# Stepper_Motor5.net
KiCad netlist of a schematic drawn in Altium Designer
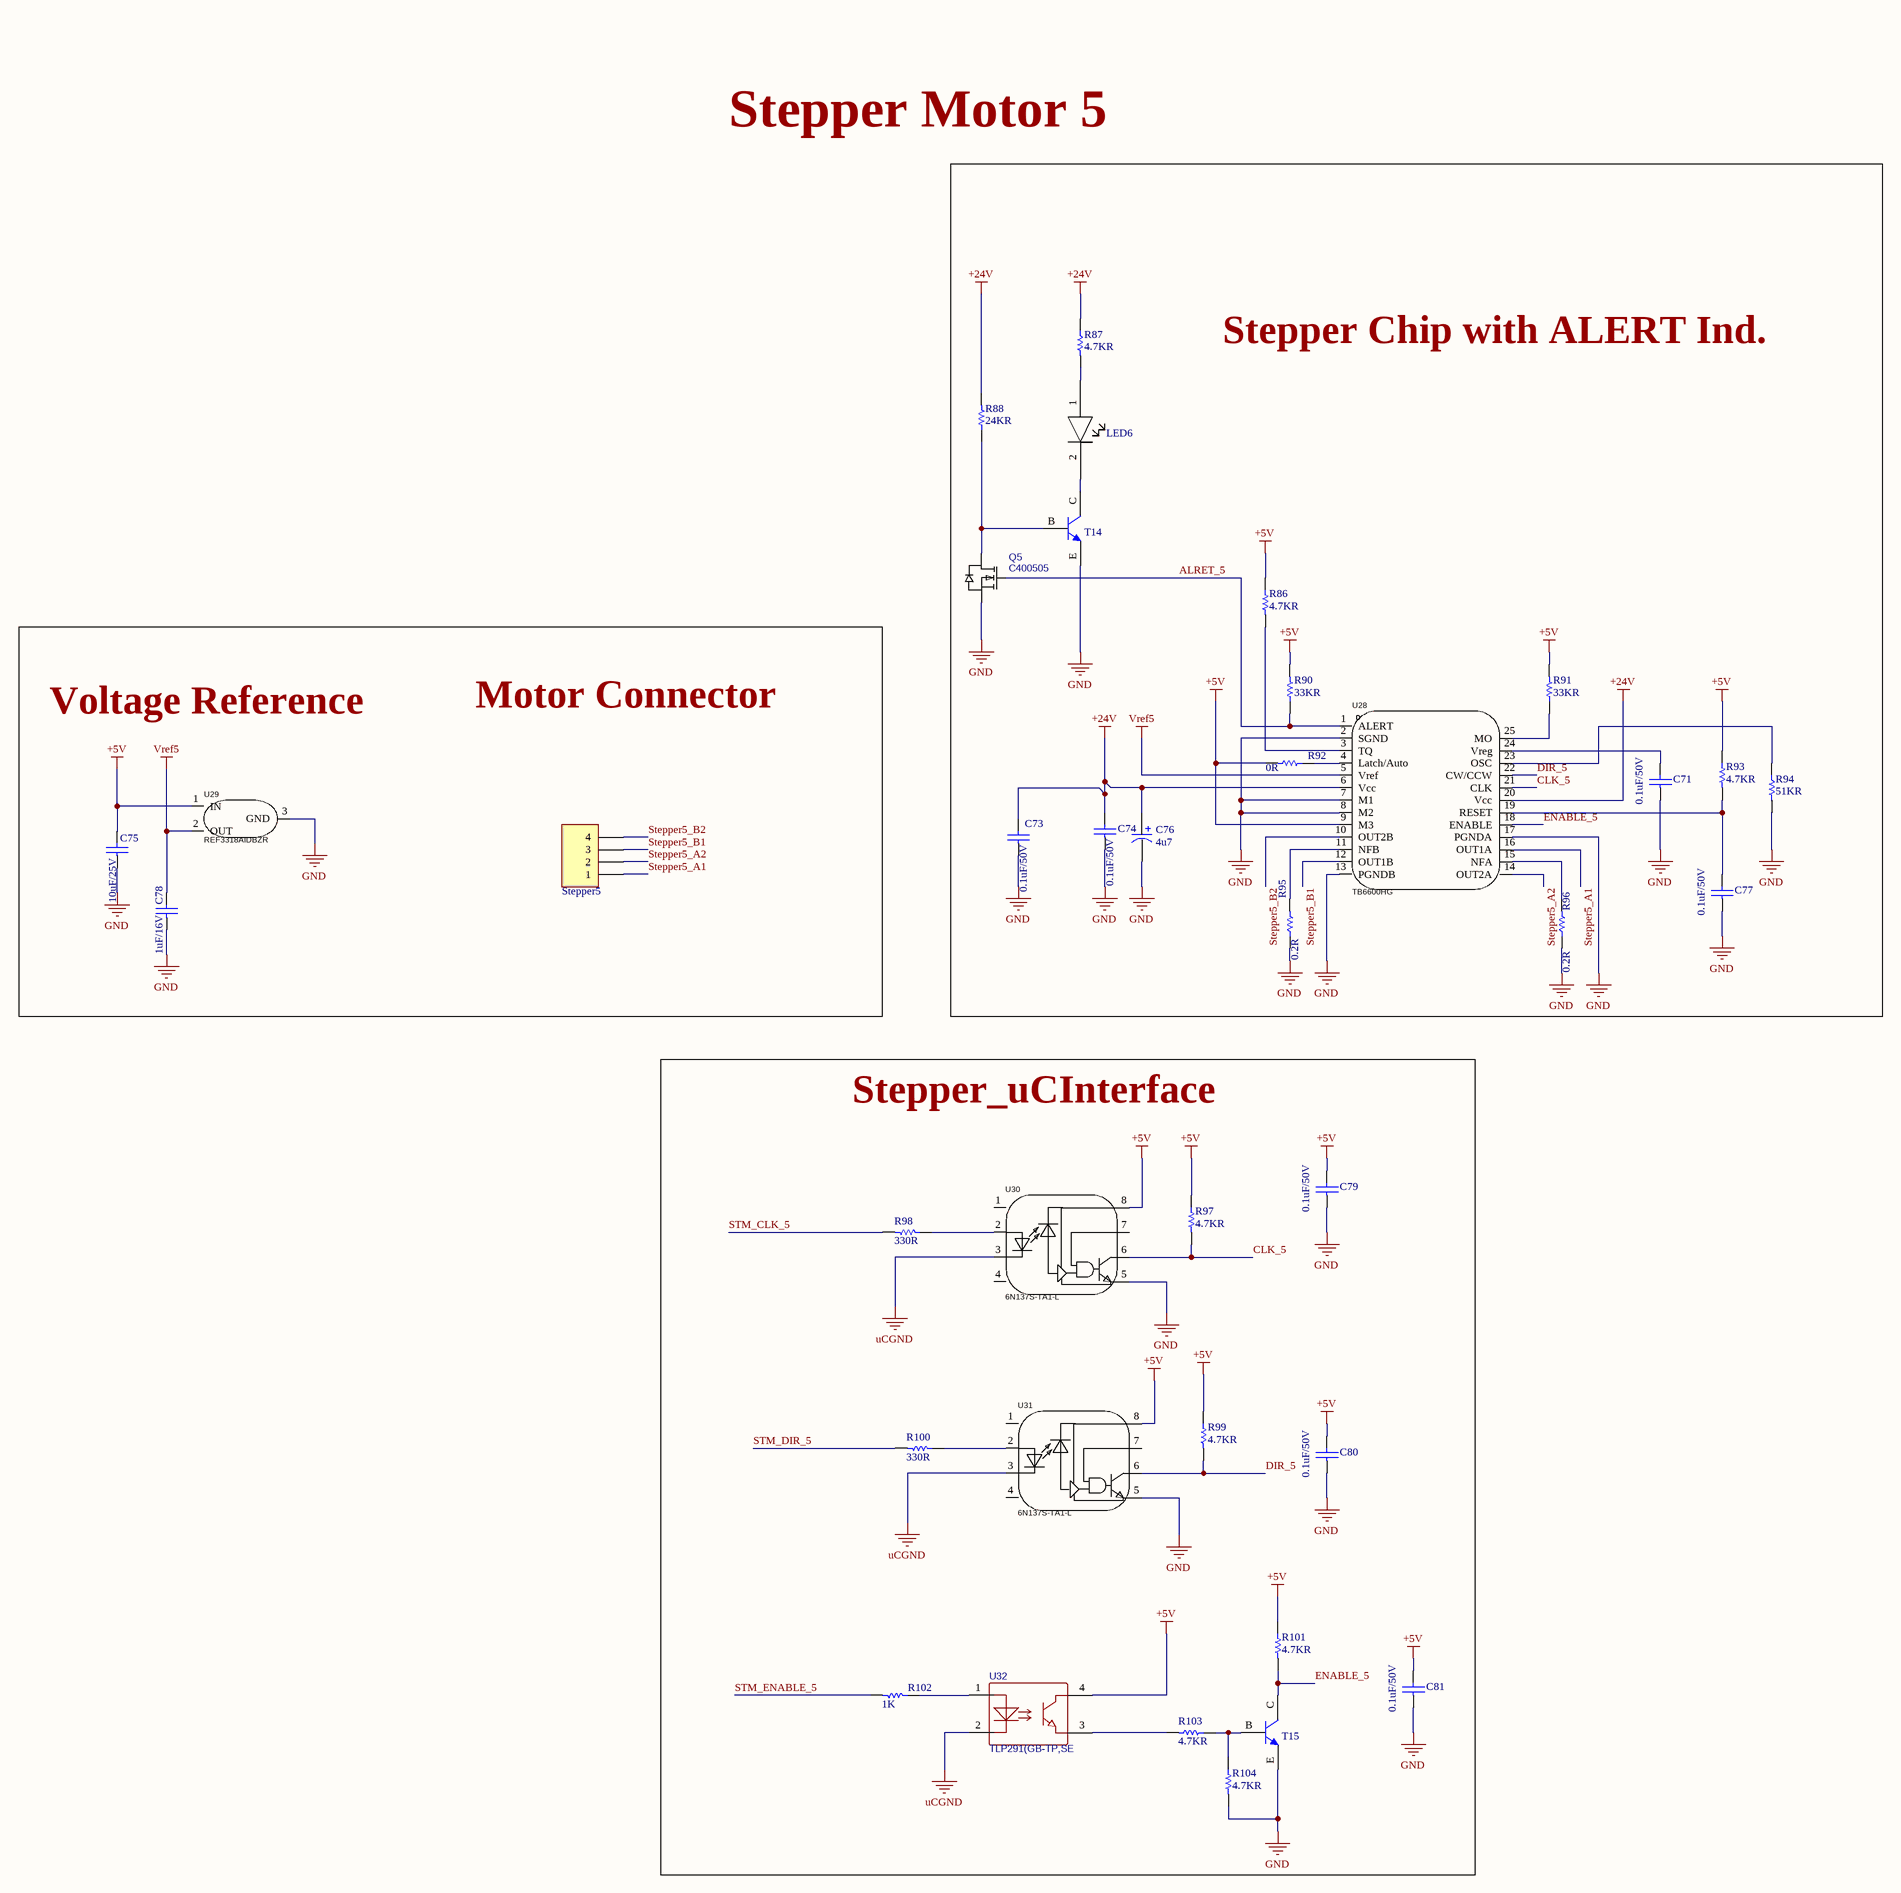
[diagram p0: Stepper Motor5.SchDoc]

(export (version "E")
  (design (tool "Eeschema 10.0.6"))
  (components
    (comp (ref "C71")
      (value "0.1uF/50V")
      (footprint "PCBComponent_1")
      (description "C1591")
      (fields (field (name "CREATED BY") "NourAldin"))
      (libsource (lib "0603 Capacitor") (part "0603 Capacitor"))
    )
    (comp (ref "C73")
      (value "0.1uF/50V")
      (footprint "PCBComponent_1")
      (description "C1591")
      (fields (field (name "CREATED BY") "NourAldin"))
      (libsource (lib "0603 Capacitor") (part "0603 Capacitor"))
    )
    (comp (ref "C74")
      (value "0.1uF/50V")
      (footprint "PCBComponent_1")
      (description "C1591")
      (fields (field (name "CREATED BY") "NourAldin"))
      (libsource (lib "0603 Capacitor") (part "0603 Capacitor"))
    )
    (comp (ref "C75")
      (value "10uF/25V")
      (footprint "PCBComponent_1")
      (description "C96446")
      (fields (field (name "CREATED BY") "NourAldin"))
      (libsource (lib "0603 Capacitor") (part "0603 Capacitor"))
    )
    (comp (ref "C76")
      (value "4u7")
      (footprint "CAPLEAD_D6.3mm")
      (description "C2691843")
      (fields
        (field (name "MANUFACTURER") "KEMET")
        (field (name "MANUFACTURER PART NUMBER") "A759EQ475M2AAAE160")
      )
      (libsource (lib "GlobalLib") (part "A759EQ475M2AAAE160"))
    )
    (comp (ref "C77")
      (value "0.1uF/50V")
      (footprint "PCBComponent_1")
      (description "C1591")
      (fields (field (name "CREATED BY") "NourAldin"))
      (libsource (lib "0603 Capacitor") (part "0603 Capacitor"))
    )
    (comp (ref "C78")
      (value "1uF/16V")
      (footprint "PCBComponent_1")
      (description "C1592")
      (fields (field (name "CREATED BY") "NourAldin"))
      (libsource (lib "0603 Capacitor") (part "0603 Capacitor"))
    )
    (comp (ref "C79")
      (value "0.1uF/50V")
      (footprint "PCBComponent_1")
      (description "C1591")
      (fields (field (name "CREATED BY") "NourAldin"))
      (libsource (lib "0603 Capacitor") (part "0603 Capacitor"))
    )
    (comp (ref "C80")
      (value "0.1uF/50V")
      (footprint "PCBComponent_1")
      (description "C1591")
      (fields (field (name "CREATED BY") "NourAldin"))
      (libsource (lib "0603 Capacitor") (part "0603 Capacitor"))
    )
    (comp (ref "C81")
      (value "0.1uF/50V")
      (footprint "PCBComponent_1")
      (description "C1591")
      (fields (field (name "CREATED BY") "NourAldin"))
      (libsource (lib "0603 Capacitor") (part "0603 Capacitor"))
    )
    (comp (ref "LED6")
      (value "1206 LED")
      (footprint "1206 LED")
      (description "C434438")
      (fields (field (name "CREATED BY") "NourAldin"))
      (libsource (lib "1206 LED") (part "1206 LED"))
    )
    (comp (ref "Q5")
      (value "C400505")
      (footprint "SOT-23-3_L2.9-W1.3-P1.90-LS2.4-BR")
      (fields
        (field (name "MANUFACTURER") "YANGJIE(扬杰)")
        (field (name "MANUFACTURER PART") "BSS138")
        (field (name "CONTRIBUTOR") "LCSC")
      )
      (libsource (lib "DIVERSE") (part "BSS138_MOSFET"))
    )
    (comp (ref "R86")
      (value "4.7KR")
      (footprint "R0402")
      (description "C105871")
      (libsource (lib "DIVERSE") (part "0402 Resistor"))
    )
    (comp (ref "R87")
      (value "4.7KR")
      (footprint "R0402")
      (description "C105871")
      (libsource (lib "DIVERSE") (part "0402 Resistor"))
    )
    (comp (ref "R88")
      (value "24KR")
      (footprint "RESC1608X06N")
      (description "C2930081")
      (fields (field (name "CREATED BY") "NourAldin"))
      (libsource (lib "0603 Resistor") (part "0603 Resistor"))
    )
    (comp (ref "R90")
      (value "33KR")
      (footprint "RESC1608X06N")
      (description "C126359")
      (fields (field (name "CREATED BY") "NourAldin"))
      (libsource (lib "0603 Resistor") (part "0603 Resistor"))
    )
    (comp (ref "R91")
      (value "33KR")
      (footprint "RESC1608X06N")
      (description "C126359")
      (fields (field (name "CREATED BY") "NourAldin"))
      (libsource (lib "0603 Resistor") (part "0603 Resistor"))
    )
    (comp (ref "R92")
      (value "0R")
      (footprint "RESC1608X06N")
      (description "C100044")
      (fields (field (name "CREATED BY") "NourAldin"))
      (libsource (lib "0603 Resistor") (part "0603 Resistor"))
    )
    (comp (ref "R93")
      (value "4.7KR")
      (footprint "R0402")
      (description "C105871")
      (libsource (lib "DIVERSE") (part "0402 Resistor"))
    )
    (comp (ref "R94")
      (value "51KR")
      (footprint "R0402")
      (description "C107230")
      (libsource (lib "DIVERSE") (part "0402 Resistor"))
    )
    (comp (ref "R95")
      (value "0.2R")
      (footprint "RESC6431X12N")
      (description "C2903473")
      (fields (field (name "CREATED BY") "NourAldin"))
      (libsource (lib "2512 Resistor") (part "2512 Resistor"))
    )
    (comp (ref "R96")
      (value "0.2R")
      (footprint "RESC6431X12N")
      (description "C2903473")
      (fields (field (name "CREATED BY") "NourAldin"))
      (libsource (lib "2512 Resistor") (part "2512 Resistor"))
    )
    (comp (ref "R97")
      (value "4.7KR")
      (footprint "R0402")
      (description "C105871")
      (libsource (lib "DIVERSE") (part "0402 Resistor"))
    )
    (comp (ref "R98")
      (value "330R")
      (footprint "R0402")
      (description "C105875")
      (libsource (lib "DIVERSE") (part "0402 Resistor"))
    )
    (comp (ref "R99")
      (value "4.7KR")
      (footprint "R0402")
      (description "C105871")
      (libsource (lib "DIVERSE") (part "0402 Resistor"))
    )
    (comp (ref "R100")
      (value "330R")
      (footprint "R0402")
      (description "C105875")
      (libsource (lib "DIVERSE") (part "0402 Resistor"))
    )
    (comp (ref "R101")
      (value "4.7KR")
      (footprint "R0402")
      (description "C105871")
      (libsource (lib "DIVERSE") (part "0402 Resistor"))
    )
    (comp (ref "R102")
      (value "1K")
      (footprint "R0402")
      (description "C106235")
      (libsource (lib "DIVERSE") (part "0402 Resistor"))
    )
    (comp (ref "R103")
      (value "4.7KR")
      (footprint "R0402")
      (description "C105871")
      (libsource (lib "DIVERSE") (part "0402 Resistor"))
    )
    (comp (ref "R104")
      (value "4.7KR")
      (footprint "R0402")
      (description "C105871")
      (libsource (lib "DIVERSE") (part "0402 Resistor"))
    )
    (comp (ref "Stepper5")
      (value "Header 4 Pin Polar")
      (footprint "PCBComponent_1")
      (description "C144395")
      (libsource (lib "Header 4 Pin Polar") (part "Header 4 Pin Polar"))
    )
    (comp (ref "T14")
      (value "MMBT3904 Transistor")
      (footprint "MMBT3904")
      (description "C108429")
      (fields (field (name "CREATED BY") "NourAldin"))
      (libsource (lib "MMBT3904 Transistor") (part "MMBT3904 Transistor"))
    )
    (comp (ref "T15")
      (value "MMBT3904 Transistor")
      (footprint "MMBT3904")
      (description "C108429")
      (fields (field (name "CREATED BY") "NourAldin"))
      (libsource (lib "MMBT3904 Transistor") (part "MMBT3904 Transistor"))
    )
    (comp (ref "U28")
      (value "TB6600HG")
      (footprint "HZIP25-P-1.0_TB6600HG - HEATSINK")
      (description "C66042")
      (fields (field (name "MANUFACTURER") "TOSHIBA(东芝)"))
      (libsource (lib "LIB") (part "TB6600HG"))
    )
    (comp (ref "U29")
      (value "REF3318AIDBZR")
      (footprint "SOT-23-3_L2.9-W1.3-P1.90-LS2.4-BR")
      (description "C115877")
      (fields (field (name "MANUFACTURER") "TI(德州仪器)") (field (name "TOLERANCE") "±0.15%"))
      (libsource (lib "LIB") (part "REF3318AIDBZR"))
    )
    (comp (ref "U30")
      (value "6N137S-TA1-L")
      (footprint "SOP-8_L9.8-W6.6-P2.54-LS10.3-BL")
      (description "C92651")
      (fields (field (name "MANUFACTURER") "LITEON(光宝)"))
      (libsource (lib "LIB") (part "6N137S-TA1-L"))
    )
    (comp (ref "U31")
      (value "6N137S-TA1-L")
      (footprint "SOP-8_L9.8-W6.6-P2.54-LS10.3-BL")
      (description "C92651")
      (fields (field (name "MANUFACTURER") "LITEON(光宝)"))
      (libsource (lib "LIB") (part "6N137S-TA1-L"))
    )
    (comp (ref "U32")
      (value "TLP291(GB-TP,SE")
      (footprint "SOP-4-1.27mm")
      (description "C55144")
      (libsource (lib "CO2_Lib") (part "TLP291(GB-TP,SE(T"))
    )
  )
  (nets
    (net (code "1") (name "+5V") (class "Default")
      (node (ref "C75") (pin "2") (pinfunction "2_2") (pintype "passive"))
      (node (ref "C79") (pin "2") (pinfunction "2_2") (pintype "passive"))
      (node (ref "C80") (pin "2") (pinfunction "2_2") (pintype "passive"))
      (node (ref "C81") (pin "2") (pinfunction "2_2") (pintype "passive"))
      (node (ref "R101") (pin "1") (pinfunction "1_1") (pintype "passive"))
      (node (ref "R86") (pin "1") (pinfunction "1_1") (pintype "passive"))
      (node (ref "R90") (pin "2") (pinfunction "2_2") (pintype "passive"))
      (node (ref "R91") (pin "2") (pinfunction "2_2") (pintype "passive"))
      (node (ref "R92") (pin "2") (pinfunction "2_2") (pintype "passive"))
      (node (ref "R93") (pin "1") (pinfunction "1_1") (pintype "passive"))
      (node (ref "R97") (pin "1") (pinfunction "1_1") (pintype "passive"))
      (node (ref "R99") (pin "1") (pinfunction "1_1") (pintype "passive"))
      (node (ref "U28") (pin "9") (pinfunction "M3_9") (pintype "passive"))
      (node (ref "U29") (pin "1") (pinfunction "IN_1") (pintype "passive"))
      (node (ref "U30") (pin "8") (pinfunction "8_8") (pintype "passive"))
      (node (ref "U31") (pin "8") (pinfunction "8_8") (pintype "passive"))
      (node (ref "U32") (pin "4") (pinfunction "4_4") (pintype "passive"))
    )
    (net (code "2") (name "+24V") (class "Default")
      (node (ref "C73") (pin "2") (pinfunction "2_2") (pintype "passive"))
      (node (ref "C74") (pin "2") (pinfunction "2_2") (pintype "passive"))
      (node (ref "C76") (pin "1") (pinfunction "1_1") (pintype "passive"))
      (node (ref "R87") (pin "1") (pinfunction "1_1") (pintype "passive"))
      (node (ref "R88") (pin "2") (pinfunction "2_2") (pintype "passive"))
      (node (ref "U28") (pin "20") (pinfunction "Vcc_20") (pintype "passive"))
      (node (ref "U28") (pin "6") (pinfunction "Vcc_6") (pintype "passive"))
    )
    (net (code "3") (name "/ALRET_5") (class "Default")
      (node (ref "Q5") (pin "1") (pinfunction "G_1") (pintype "passive"))
      (node (ref "R90") (pin "1") (pinfunction "1_1") (pintype "passive"))
      (node (ref "U28") (pin "1") (pinfunction "ALERT_1") (pintype "passive"))
    )
    (net (code "4") (name "/CLK_5") (class "Default")
      (node (ref "R97") (pin "2") (pinfunction "2_2") (pintype "passive"))
      (node (ref "U28") (pin "21") (pinfunction "CLK_21") (pintype "passive"))
      (node (ref "U30") (pin "6") (pinfunction "6_6") (pintype "passive"))
    )
    (net (code "5") (name "/DIR_5") (class "Default")
      (node (ref "R99") (pin "2") (pinfunction "2_2") (pintype "passive"))
      (node (ref "U28") (pin "22") (pinfunction "CW/CCW_22") (pintype "passive"))
      (node (ref "U31") (pin "6") (pinfunction "6_6") (pintype "passive"))
    )
    (net (code "6") (name "/ENABLE_5") (class "Default")
      (node (ref "R101") (pin "2") (pinfunction "2_2") (pintype "passive"))
      (node (ref "T15") (pin "C") (pinfunction "C_C") (pintype "passive"))
      (node (ref "U28") (pin "18") (pinfunction "ENABLE_18") (pintype "passive"))
    )
    (net (code "7") (name "/STM_CLK_5") (class "Default")
      (node (ref "R98") (pin "2") (pinfunction "2_2") (pintype "passive"))
    )
    (net (code "8") (name "/STM_DIR_5") (class "Default")
      (node (ref "R100") (pin "2") (pinfunction "2_2") (pintype "passive"))
    )
    (net (code "9") (name "/STM_ENABLE_5") (class "Default")
      (node (ref "R102") (pin "2") (pinfunction "2_2") (pintype "passive"))
    )
    (net (code "10") (name "/Stepper5_A1") (class "Default")
      (node (ref "Stepper5") (pin "1") (pinfunction "1_1") (pintype "passive"))
      (node (ref "U28") (pin "16") (pinfunction "OUT1A_16") (pintype "passive"))
    )
    (net (code "11") (name "/Stepper5_A2") (class "Default")
      (node (ref "Stepper5") (pin "2") (pinfunction "2_2") (pintype "passive"))
      (node (ref "U28") (pin "14") (pinfunction "OUT2A_14") (pintype "passive"))
    )
    (net (code "12") (name "/Stepper5_B1") (class "Default")
      (node (ref "Stepper5") (pin "3") (pinfunction "3_3") (pintype "passive"))
      (node (ref "U28") (pin "12") (pinfunction "OUT1B_12") (pintype "passive"))
    )
    (net (code "13") (name "/Stepper5_B2") (class "Default")
      (node (ref "Stepper5") (pin "4") (pinfunction "4_4") (pintype "passive"))
      (node (ref "U28") (pin "10") (pinfunction "OUT2B_10") (pintype "passive"))
    )
    (net (code "14") (name "GND") (class "Default")
      (node (ref "C71") (pin "1") (pinfunction "1_1") (pintype "passive"))
      (node (ref "C73") (pin "1") (pinfunction "1_1") (pintype "passive"))
      (node (ref "C74") (pin "1") (pinfunction "1_1") (pintype "passive"))
      (node (ref "C75") (pin "1") (pinfunction "1_1") (pintype "passive"))
      (node (ref "C76") (pin "2") (pinfunction "2_2") (pintype "passive"))
      (node (ref "C77") (pin "1") (pinfunction "1_1") (pintype "passive"))
      (node (ref "C78") (pin "1") (pinfunction "1_1") (pintype "passive"))
      (node (ref "C79") (pin "1") (pinfunction "1_1") (pintype "passive"))
      (node (ref "C80") (pin "1") (pinfunction "1_1") (pintype "passive"))
      (node (ref "C81") (pin "1") (pinfunction "1_1") (pintype "passive"))
      (node (ref "Q5") (pin "2") (pinfunction "S_2") (pintype "passive"))
      (node (ref "R104") (pin "2") (pinfunction "2_2") (pintype "passive"))
      (node (ref "R94") (pin "2") (pinfunction "2_2") (pintype "passive"))
      (node (ref "R95") (pin "1") (pinfunction "1_1") (pintype "passive"))
      (node (ref "R96") (pin "1") (pinfunction "1_1") (pintype "passive"))
      (node (ref "T14") (pin "E") (pinfunction "E_E") (pintype "passive"))
      (node (ref "T15") (pin "E") (pinfunction "E_E") (pintype "passive"))
      (node (ref "U28") (pin "13") (pinfunction "PGNDB_13") (pintype "passive"))
      (node (ref "U28") (pin "17") (pinfunction "PGNDA_17") (pintype "passive"))
      (node (ref "U28") (pin "2") (pinfunction "SGND_2") (pintype "passive"))
      (node (ref "U28") (pin "7") (pinfunction "M1_7") (pintype "passive"))
      (node (ref "U28") (pin "8") (pinfunction "M2_8") (pintype "passive"))
      (node (ref "U29") (pin "3") (pinfunction "GND_3") (pintype "passive"))
      (node (ref "U30") (pin "5") (pinfunction "5_5") (pintype "passive"))
      (node (ref "U31") (pin "5") (pinfunction "5_5") (pintype "passive"))
    )
    (net (code "15") (name "Net-(LED6-Pad1)") (class "Default")
      (node (ref "LED6") (pin "1") (pinfunction "1_1") (pintype "passive"))
      (node (ref "R87") (pin "2") (pinfunction "2_2") (pintype "passive"))
    )
    (net (code "16") (name "Net-(LED6-Pad2)") (class "Default")
      (node (ref "LED6") (pin "2") (pinfunction "2_2") (pintype "passive"))
      (node (ref "T14") (pin "C") (pinfunction "C_C") (pintype "passive"))
    )
    (net (code "17") (name "Net-(Q5-D)") (class "Default")
      (node (ref "Q5") (pin "3") (pinfunction "D_3") (pintype "passive"))
      (node (ref "R88") (pin "1") (pinfunction "1_1") (pintype "passive"))
      (node (ref "T14") (pin "B") (pinfunction "B_B") (pintype "passive"))
    )
    (net (code "18") (name "Net-(R98-Pad1)") (class "Default")
      (node (ref "R98") (pin "1") (pinfunction "1_1") (pintype "passive"))
      (node (ref "U30") (pin "2") (pinfunction "2_2") (pintype "passive"))
    )
    (net (code "19") (name "Net-(R100-Pad1)") (class "Default")
      (node (ref "R100") (pin "1") (pinfunction "1_1") (pintype "passive"))
      (node (ref "U31") (pin "2") (pinfunction "2_2") (pintype "passive"))
    )
    (net (code "20") (name "Net-(R102-Pad1)") (class "Default")
      (node (ref "R102") (pin "1") (pinfunction "1_1") (pintype "passive"))
      (node (ref "U32") (pin "1") (pinfunction "1_1") (pintype "passive"))
    )
    (net (code "21") (name "Net-(R103-Pad1)") (class "Default")
      (node (ref "R103") (pin "1") (pinfunction "1_1") (pintype "passive"))
      (node (ref "R104") (pin "1") (pinfunction "1_1") (pintype "passive"))
      (node (ref "T15") (pin "B") (pinfunction "B_B") (pintype "passive"))
    )
    (net (code "22") (name "Net-(R103-Pad2)") (class "Default")
      (node (ref "R103") (pin "2") (pinfunction "2_2") (pintype "passive"))
      (node (ref "U32") (pin "3") (pinfunction "3_3") (pintype "passive"))
    )
    (net (code "23") (name "Net-(U28-Latch{slash}Auto)") (class "Default")
      (node (ref "R92") (pin "1") (pinfunction "1_1") (pintype "passive"))
      (node (ref "U28") (pin "4") (pinfunction "Latch/Auto_4") (pintype "passive"))
    )
    (net (code "24") (name "Net-(U28-MO)") (class "Default")
      (node (ref "R91") (pin "1") (pinfunction "1_1") (pintype "passive"))
      (node (ref "U28") (pin "25") (pinfunction "MO_25") (pintype "passive"))
    )
    (net (code "25") (name "Net-(U28-NFA)") (class "Default")
      (node (ref "R96") (pin "2") (pinfunction "2_2") (pintype "passive"))
      (node (ref "U28") (pin "15") (pinfunction "NFA_15") (pintype "passive"))
    )
    (net (code "26") (name "Net-(U28-NFB)") (class "Default")
      (node (ref "R95") (pin "2") (pinfunction "2_2") (pintype "passive"))
      (node (ref "U28") (pin "11") (pinfunction "NFB_11") (pintype "passive"))
    )
    (net (code "27") (name "Net-(U28-OSC)") (class "Default")
      (node (ref "R94") (pin "1") (pinfunction "1_1") (pintype "passive"))
      (node (ref "U28") (pin "23") (pinfunction "OSC_23") (pintype "passive"))
    )
    (net (code "28") (name "Net-(U28-RESET)") (class "Default")
      (node (ref "C77") (pin "2") (pinfunction "2_2") (pintype "passive"))
      (node (ref "R93") (pin "2") (pinfunction "2_2") (pintype "passive"))
      (node (ref "U28") (pin "19") (pinfunction "RESET_19") (pintype "passive"))
    )
    (net (code "29") (name "Net-(U28-TQ)") (class "Default")
      (node (ref "R86") (pin "2") (pinfunction "2_2") (pintype "passive"))
      (node (ref "U28") (pin "3") (pinfunction "TQ_3") (pintype "passive"))
    )
    (net (code "30") (name "Net-(U28-Vreg)") (class "Default")
      (node (ref "C71") (pin "2") (pinfunction "2_2") (pintype "passive"))
      (node (ref "U28") (pin "24") (pinfunction "Vreg_24") (pintype "passive"))
    )
    (net (code "31") (name "Vref5") (class "Default")
      (node (ref "C78") (pin "2") (pinfunction "2_2") (pintype "passive"))
      (node (ref "U28") (pin "5") (pinfunction "Vref_5") (pintype "passive"))
      (node (ref "U29") (pin "2") (pinfunction "OUT_2") (pintype "passive"))
    )
    (net (code "32") (name "uCGND") (class "Default")
      (node (ref "U30") (pin "3") (pinfunction "3_3") (pintype "passive"))
      (node (ref "U31") (pin "3") (pinfunction "3_3") (pintype "passive"))
      (node (ref "U32") (pin "2") (pinfunction "2_2") (pintype "passive"))
    )
    (net (code "33") (name "unconnected-(U30-NC-Pad1)") (class "Default")
      (node (ref "U30") (pin "1") (pinfunction "NC_1") (pintype "passive"))
    )
    (net (code "34") (name "unconnected-(U30-NC-Pad4)") (class "Default")
      (node (ref "U30") (pin "4") (pinfunction "NC_4") (pintype "passive"))
    )
    (net (code "35") (name "unconnected-(U30-Pad7)") (class "Default")
      (node (ref "U30") (pin "7") (pinfunction "7_7") (pintype "passive"))
    )
    (net (code "36") (name "unconnected-(U31-NC-Pad1)") (class "Default")
      (node (ref "U31") (pin "1") (pinfunction "NC_1") (pintype "passive"))
    )
    (net (code "37") (name "unconnected-(U31-NC-Pad4)") (class "Default")
      (node (ref "U31") (pin "4") (pinfunction "NC_4") (pintype "passive"))
    )
    (net (code "38") (name "unconnected-(U31-Pad7)") (class "Default")
      (node (ref "U31") (pin "7") (pinfunction "7_7") (pintype "passive"))
    )
  )
)
